# Volt_meter.net
KiCad netlist of a schematic drawn in Altium Designer
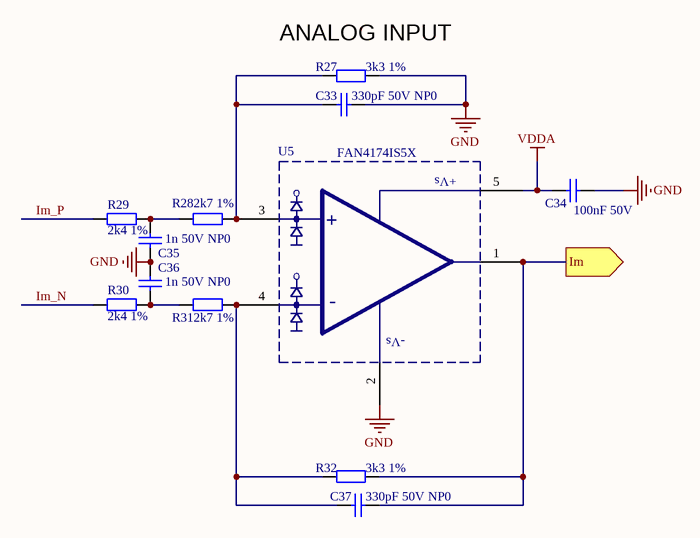
[diagram p0: Volt_meter.SchDoc]

(export (version "E")
  (design (tool "Eeschema 10.0.6"))
  (components
    (comp (ref "C33")
      (value "330pF 50V NP0")
      (footprint "0805_C")
      (description "SMD kondenzátorok")
      (libsource (lib "MERES") (part "Capacitor_SMD"))
    )
    (comp (ref "C34")
      (value "100nF 50V")
      (footprint "0805_C")
      (description "SMD kondenzátorok")
      (libsource (lib "MERES") (part "Capacitor_SMD"))
    )
    (comp (ref "C35")
      (value "1n 50V NP0")
      (footprint "0805_C")
      (libsource (lib "MERES") (part "Capacitor_SMD"))
    )
    (comp (ref "C36")
      (value "1n 50V NP0")
      (footprint "0805_C")
      (libsource (lib "MERES") (part "Capacitor_SMD"))
    )
    (comp (ref "C37")
      (value "330pF 50V NP0")
      (footprint "0805_C")
      (description "SMD kondenzátorok")
      (libsource (lib "MERES") (part "Capacitor_SMD"))
    )
    (comp (ref "R27")
      (value "3k3 1%")
      (footprint "MELF_RES_LARGE")
      (libsource (lib "MERES") (part "Resistor"))
    )
    (comp (ref "R28")
      (value "2k7 1%")
      (footprint "MELF_RES_LARGE")
      (libsource (lib "MERES") (part "Resistor"))
    )
    (comp (ref "R29")
      (value "2k4 1%")
      (footprint "MELF_RES_LARGE")
      (libsource (lib "MERES") (part "Resistor"))
    )
    (comp (ref "R30")
      (value "2k4 1%")
      (footprint "MELF_RES_LARGE")
      (libsource (lib "MERES") (part "Resistor"))
    )
    (comp (ref "R31")
      (value "2k7 1%")
      (footprint "MELF_RES_LARGE")
      (libsource (lib "MERES") (part "Resistor"))
    )
    (comp (ref "R32")
      (value "3k3 1%")
      (footprint "MELF_RES_LARGE")
      (libsource (lib "MERES") (part "Resistor"))
    )
    (comp (ref "U5")
      (value "FAN4174IS5X")
      (footprint "SOT-23-5")
      (libsource (lib "MERES") (part "FAN4174IS5X"))
    )
  )
  (nets
    (net (code "1") (name "/Im") (class "Default")
      (node (ref "C37") (pin "2") (pinfunction "2_2") (pintype "passive"))
      (node (ref "R32") (pin "1") (pinfunction "1_1") (pintype "passive"))
      (node (ref "U5") (pin "1") (pinfunction "OUT_1") (pintype "passive"))
    )
    (net (code "2") (name "/Im_N") (class "Default")
      (node (ref "R30") (pin "2") (pinfunction "2_2") (pintype "passive"))
    )
    (net (code "3") (name "/Im_P") (class "Default")
      (node (ref "R29") (pin "2") (pinfunction "2_2") (pintype "passive"))
    )
    (net (code "4") (name "GND") (class "Default")
      (node (ref "C33") (pin "2") (pinfunction "2_2") (pintype "passive"))
      (node (ref "C34") (pin "1") (pinfunction "1_1") (pintype "passive"))
      (node (ref "C35") (pin "1") (pinfunction "1_1") (pintype "passive"))
      (node (ref "C36") (pin "2") (pinfunction "2_2") (pintype "passive"))
      (node (ref "R27") (pin "1") (pinfunction "1_1") (pintype "passive"))
      (node (ref "U5") (pin "2") (pinfunction "-Vs_2") (pintype "passive"))
    )
    (net (code "5") (name "Net-(C35-Pad2)") (class "Default")
      (node (ref "C35") (pin "2") (pinfunction "2_2") (pintype "passive"))
      (node (ref "R28") (pin "2") (pinfunction "2_2") (pintype "passive"))
      (node (ref "R29") (pin "1") (pinfunction "1_1") (pintype "passive"))
    )
    (net (code "6") (name "Net-(C36-Pad1)") (class "Default")
      (node (ref "C36") (pin "1") (pinfunction "1_1") (pintype "passive"))
      (node (ref "R30") (pin "1") (pinfunction "1_1") (pintype "passive"))
      (node (ref "R31") (pin "2") (pinfunction "2_2") (pintype "passive"))
    )
    (net (code "7") (name "Net-(U5-+IN)") (class "Default")
      (node (ref "C33") (pin "1") (pinfunction "1_1") (pintype "passive"))
      (node (ref "R27") (pin "2") (pinfunction "2_2") (pintype "passive"))
      (node (ref "R28") (pin "1") (pinfunction "1_1") (pintype "passive"))
      (node (ref "U5") (pin "3") (pinfunction "+IN_3") (pintype "passive"))
    )
    (net (code "8") (name "Net-(U5--IN)") (class "Default")
      (node (ref "C37") (pin "1") (pinfunction "1_1") (pintype "passive"))
      (node (ref "R31") (pin "1") (pinfunction "1_1") (pintype "passive"))
      (node (ref "R32") (pin "2") (pinfunction "2_2") (pintype "passive"))
      (node (ref "U5") (pin "4") (pinfunction "-IN_4") (pintype "passive"))
    )
    (net (code "9") (name "VDDA") (class "Default")
      (node (ref "C34") (pin "2") (pinfunction "2_2") (pintype "passive"))
      (node (ref "U5") (pin "5") (pinfunction "+Vs_5") (pintype "passive"))
    )
  )
)
